# IN_OUT_BIT_7.net
KiCad netlist of a schematic drawn in EasyEDA
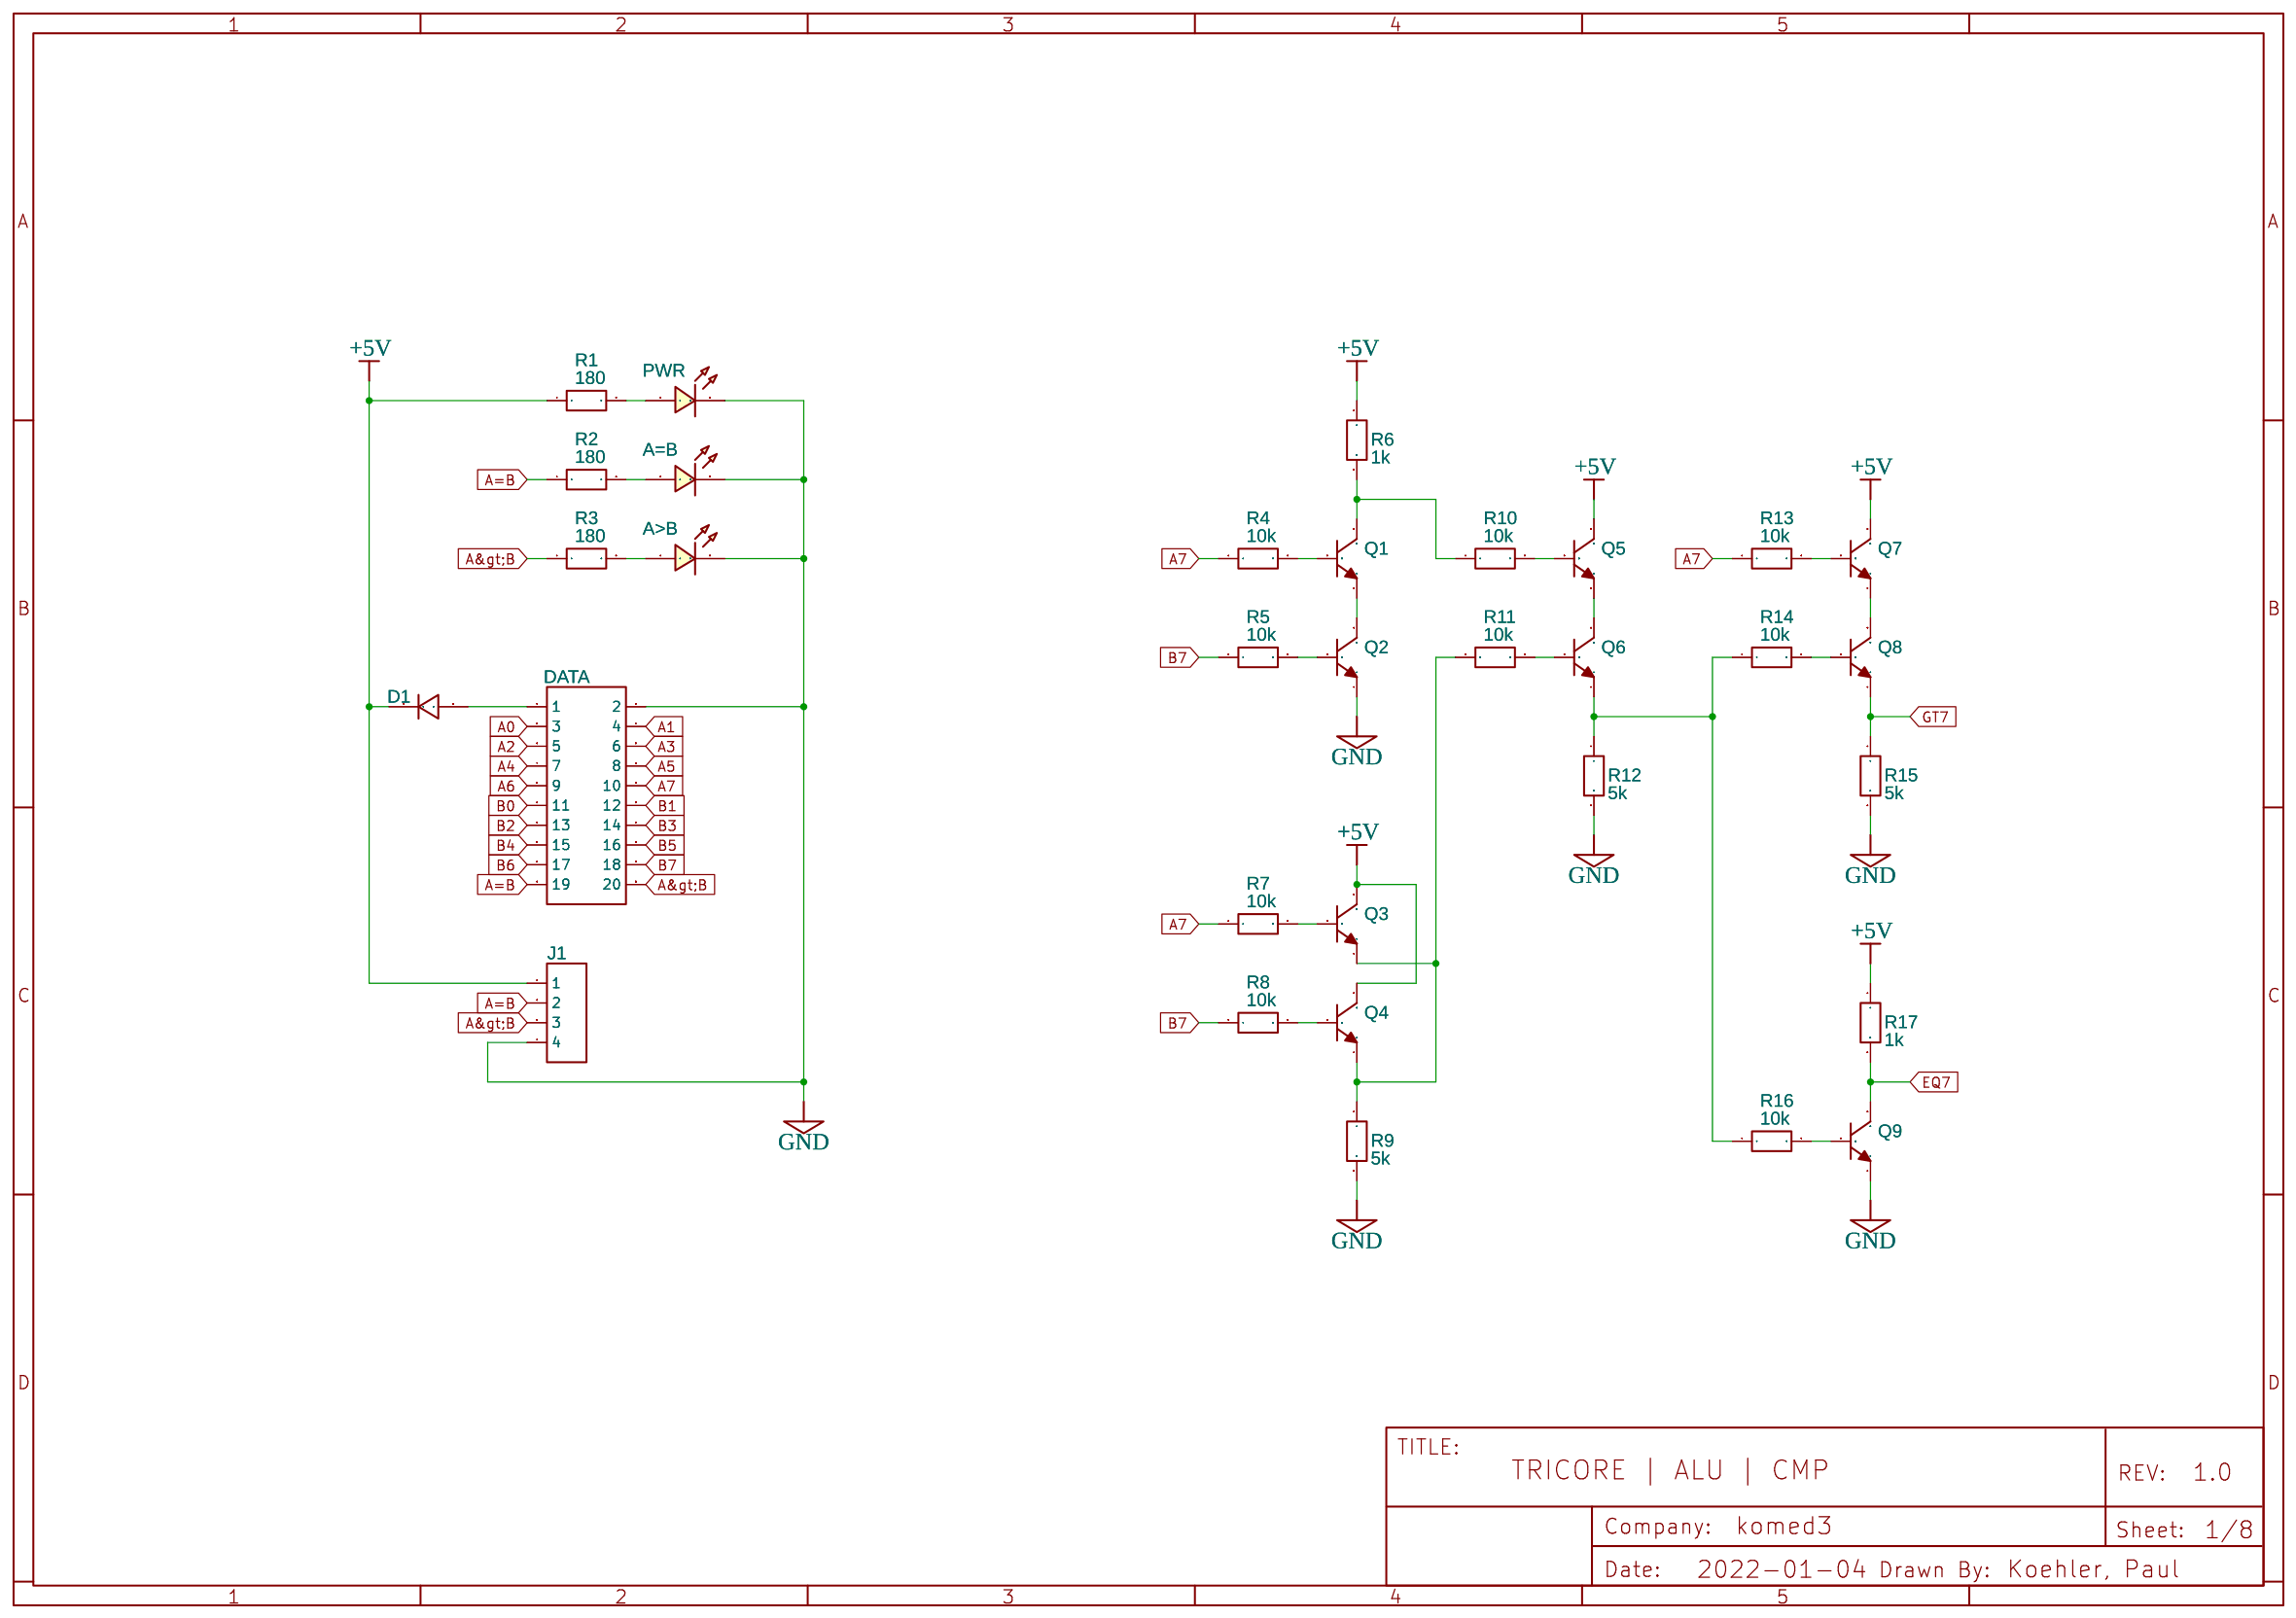
[diagram p0: schematic sheet]

(export (version "E")
  (design (tool "Eeschema 10.0.6"))
  (components
    (comp (ref "A=B")
      (value "LED-TH-5mm_R")
      (fields
        (field (name "BOM_Manufacturer Part") "333-2SURD/S530-A3")
        (field (name "BOM_Supplier Part") "C87271")
      )
      (libsource (lib "") (part "LED-TH-5mm_R"))
    )
    (comp (ref "A>B")
      (value "LED-TH-5mm_R")
      (fields
        (field (name "BOM_Manufacturer Part") "333-2SURD/S530-A3")
        (field (name "BOM_Supplier Part") "C87271")
      )
      (libsource (lib "") (part "LED-TH-5mm_R_1"))
    )
    (comp (ref "D1")
      (value "1N4007")
      (fields (field (name "BOM_Supplier Part") "C106903"))
      (libsource (lib "") (part "1N4007"))
    )
    (comp (ref "DATA")
      (value "HDR-IDC-2.54-2X10P")
      (fields
        (field (name "BOM_Manufacturer Part") "IDC Box 2.54mm 2X10P　Straight")
        (field (name "BOM_Supplier Part") "C3405")
      )
      (libsource (lib "") (part "HDR-IDC-2.54-2X10P"))
    )
    (comp (ref "J1")
      (value "HDR-M-2.54_1x4")
      (fields (field (name "BOM_Supplier Part") "C124378"))
      (libsource (lib "") (part "HDR-M-2.54_1x4"))
    )
    (comp (ref "PWR")
      (value "LED-TH-5mm_R")
      (fields
        (field (name "BOM_Manufacturer Part") "333-2SURD/S530-A3")
        (field (name "BOM_Supplier Part") "C87271")
      )
      (libsource (lib "") (part "LED-TH-5mm_R_2"))
    )
    (comp (ref "Q1")
      (value "2N3904(TO-92)")
      (fields (field (name "BOM_Manufacturer Part") "2N3904") (field (name "BOM_Supplier Part") "C118538"))
      (libsource (lib "") (part "2N3904(TO-92)"))
    )
    (comp (ref "Q2")
      (value "2N3904(TO-92)")
      (fields (field (name "BOM_Manufacturer Part") "2N3904") (field (name "BOM_Supplier Part") "C118538"))
      (libsource (lib "") (part "2N3904(TO-92)"))
    )
    (comp (ref "Q3")
      (value "2N3904(TO-92)")
      (fields (field (name "BOM_Manufacturer Part") "2N3904") (field (name "BOM_Supplier Part") "C118538"))
      (libsource (lib "") (part "2N3904(TO-92)"))
    )
    (comp (ref "Q4")
      (value "2N3904(TO-92)")
      (fields (field (name "BOM_Manufacturer Part") "2N3904") (field (name "BOM_Supplier Part") "C118538"))
      (libsource (lib "") (part "2N3904(TO-92)"))
    )
    (comp (ref "Q5")
      (value "2N3904(TO-92)")
      (fields (field (name "BOM_Manufacturer Part") "2N3904") (field (name "BOM_Supplier Part") "C118538"))
      (libsource (lib "") (part "2N3904(TO-92)"))
    )
    (comp (ref "Q6")
      (value "2N3904(TO-92)")
      (fields (field (name "BOM_Manufacturer Part") "2N3904") (field (name "BOM_Supplier Part") "C118538"))
      (libsource (lib "") (part "2N3904(TO-92)"))
    )
    (comp (ref "Q7")
      (value "2N3904(TO-92)")
      (fields (field (name "BOM_Manufacturer Part") "2N3904") (field (name "BOM_Supplier Part") "C118538"))
      (libsource (lib "") (part "2N3904(TO-92)"))
    )
    (comp (ref "Q8")
      (value "2N3904(TO-92)")
      (fields (field (name "BOM_Manufacturer Part") "2N3904") (field (name "BOM_Supplier Part") "C118538"))
      (libsource (lib "") (part "2N3904(TO-92)"))
    )
    (comp (ref "Q9")
      (value "2N3904(TO-92)")
      (fields (field (name "BOM_Manufacturer Part") "2N3904") (field (name "BOM_Supplier Part") "C118538"))
      (libsource (lib "") (part "2N3904(TO-92)"))
    )
    (comp (ref "R1") (value "180") (libsource (lib "") (part "R_AXIAL-0.3_EU")))
    (comp (ref "R2") (value "180") (libsource (lib "") (part "R_AXIAL-0.3_EU")))
    (comp (ref "R3") (value "180") (libsource (lib "") (part "R_AXIAL-0.3_EU")))
    (comp (ref "R4") (value "10k") (libsource (lib "") (part "R_AXIAL-0.3_EU")))
    (comp (ref "R5") (value "10k") (libsource (lib "") (part "R_AXIAL-0.3_EU")))
    (comp (ref "R6") (value "1k") (libsource (lib "") (part "R_AXIAL-0.3_EU_1")))
    (comp (ref "R7") (value "10k") (libsource (lib "") (part "R_AXIAL-0.3_EU")))
    (comp (ref "R8") (value "10k") (libsource (lib "") (part "R_AXIAL-0.3_EU")))
    (comp (ref "R9") (value "5k") (libsource (lib "") (part "R_AXIAL-0.3_EU_1")))
    (comp (ref "R10") (value "10k") (libsource (lib "") (part "R_AXIAL-0.3_EU")))
    (comp (ref "R11") (value "10k") (libsource (lib "") (part "R_AXIAL-0.3_EU")))
    (comp (ref "R12") (value "5k") (libsource (lib "") (part "R_AXIAL-0.3_EU_1")))
    (comp (ref "R13") (value "10k") (libsource (lib "") (part "R_AXIAL-0.3_EU")))
    (comp (ref "R14") (value "10k") (libsource (lib "") (part "R_AXIAL-0.3_EU")))
    (comp (ref "R15") (value "5k") (libsource (lib "") (part "R_AXIAL-0.3_EU_1")))
    (comp (ref "R16") (value "10k") (libsource (lib "") (part "R_AXIAL-0.3_EU")))
    (comp (ref "R17") (value "1k") (libsource (lib "") (part "R_AXIAL-0.3_EU_1")))
  )
  (nets
    (net (code "1") (name "+5V") (class "Default")
      (node (ref "D1") (pin "1") (pinfunction "1_1") (pintype "unspecified"))
      (node (ref "J1") (pin "1") (pinfunction "1_1") (pintype "unspecified"))
      (node (ref "Q3") (pin "3") (pinfunction "C_3") (pintype "unspecified"))
      (node (ref "Q4") (pin "3") (pinfunction "C_3") (pintype "unspecified"))
      (node (ref "Q5") (pin "3") (pinfunction "C_3") (pintype "unspecified"))
      (node (ref "Q7") (pin "3") (pinfunction "C_3") (pintype "unspecified"))
      (node (ref "R1") (pin "1") (pinfunction "1_1") (pintype "unspecified"))
      (node (ref "R17") (pin "1") (pinfunction "1_1") (pintype "unspecified"))
      (node (ref "R6") (pin "1") (pinfunction "1_1") (pintype "unspecified"))
    )
    (net (code "2") (name "A&gt;B") (class "Default")
      (node (ref "DATA") (pin "20") (pinfunction "20_20") (pintype "unspecified"))
      (node (ref "J1") (pin "3") (pinfunction "3_3") (pintype "unspecified"))
      (node (ref "R3") (pin "1") (pinfunction "1_1") (pintype "unspecified"))
    )
    (net (code "3") (name "A0") (class "Default")
      (node (ref "DATA") (pin "3") (pinfunction "3_3") (pintype "unspecified"))
    )
    (net (code "4") (name "A1") (class "Default")
      (node (ref "DATA") (pin "4") (pinfunction "4_4") (pintype "unspecified"))
    )
    (net (code "5") (name "A2") (class "Default")
      (node (ref "DATA") (pin "5") (pinfunction "5_5") (pintype "unspecified"))
    )
    (net (code "6") (name "A3") (class "Default")
      (node (ref "DATA") (pin "6") (pinfunction "6_6") (pintype "unspecified"))
    )
    (net (code "7") (name "A4") (class "Default")
      (node (ref "DATA") (pin "7") (pinfunction "7_7") (pintype "unspecified"))
    )
    (net (code "8") (name "A5") (class "Default")
      (node (ref "DATA") (pin "8") (pinfunction "8_8") (pintype "unspecified"))
    )
    (net (code "9") (name "A6") (class "Default")
      (node (ref "DATA") (pin "9") (pinfunction "9_9") (pintype "unspecified"))
    )
    (net (code "10") (name "A7") (class "Default")
      (node (ref "DATA") (pin "10") (pinfunction "10_10") (pintype "unspecified"))
      (node (ref "R13") (pin "1") (pinfunction "1_1") (pintype "unspecified"))
      (node (ref "R4") (pin "1") (pinfunction "1_1") (pintype "unspecified"))
      (node (ref "R7") (pin "1") (pinfunction "1_1") (pintype "unspecified"))
    )
    (net (code "11") (name "A=B") (class "Default")
      (node (ref "DATA") (pin "19") (pinfunction "19_19") (pintype "unspecified"))
      (node (ref "J1") (pin "2") (pinfunction "2_2") (pintype "unspecified"))
      (node (ref "R2") (pin "1") (pinfunction "1_1") (pintype "unspecified"))
    )
    (net (code "12") (name "B0") (class "Default")
      (node (ref "DATA") (pin "11") (pinfunction "11_11") (pintype "unspecified"))
    )
    (net (code "13") (name "B1") (class "Default")
      (node (ref "DATA") (pin "12") (pinfunction "12_12") (pintype "unspecified"))
    )
    (net (code "14") (name "B2") (class "Default")
      (node (ref "DATA") (pin "13") (pinfunction "13_13") (pintype "unspecified"))
    )
    (net (code "15") (name "B3") (class "Default")
      (node (ref "DATA") (pin "14") (pinfunction "14_14") (pintype "unspecified"))
    )
    (net (code "16") (name "B4") (class "Default")
      (node (ref "DATA") (pin "15") (pinfunction "15_15") (pintype "unspecified"))
    )
    (net (code "17") (name "B5") (class "Default")
      (node (ref "DATA") (pin "16") (pinfunction "16_16") (pintype "unspecified"))
    )
    (net (code "18") (name "B6") (class "Default")
      (node (ref "DATA") (pin "17") (pinfunction "17_17") (pintype "unspecified"))
    )
    (net (code "19") (name "B7") (class "Default")
      (node (ref "DATA") (pin "18") (pinfunction "18_18") (pintype "unspecified"))
      (node (ref "R5") (pin "1") (pinfunction "1_1") (pintype "unspecified"))
      (node (ref "R8") (pin "1") (pinfunction "1_1") (pintype "unspecified"))
    )
    (net (code "20") (name "EQ7") (class "Default")
      (node (ref "Q9") (pin "3") (pinfunction "C_3") (pintype "unspecified"))
      (node (ref "R17") (pin "2") (pinfunction "2_2") (pintype "unspecified"))
    )
    (net (code "21") (name "GND") (class "Default")
      (node (ref "A=B") (pin "2") (pinfunction "2_2") (pintype "unspecified"))
      (node (ref "A>B") (pin "2") (pinfunction "2_2") (pintype "unspecified"))
      (node (ref "DATA") (pin "2") (pinfunction "2_2") (pintype "unspecified"))
      (node (ref "J1") (pin "4") (pinfunction "4_4") (pintype "unspecified"))
      (node (ref "PWR") (pin "2") (pinfunction "2_2") (pintype "unspecified"))
      (node (ref "Q2") (pin "1") (pinfunction "E_1") (pintype "unspecified"))
      (node (ref "Q9") (pin "1") (pinfunction "E_1") (pintype "unspecified"))
      (node (ref "R12") (pin "2") (pinfunction "2_2") (pintype "unspecified"))
      (node (ref "R15") (pin "2") (pinfunction "2_2") (pintype "unspecified"))
      (node (ref "R9") (pin "2") (pinfunction "2_2") (pintype "unspecified"))
    )
    (net (code "22") (name "GT7") (class "Default")
      (node (ref "Q8") (pin "1") (pinfunction "E_1") (pintype "unspecified"))
      (node (ref "R15") (pin "1") (pinfunction "1_1") (pintype "unspecified"))
    )
    (net (code "23") (name "Net-(A=B-Pad1)") (class "Default")
      (node (ref "A=B") (pin "1") (pinfunction "1_1") (pintype "unspecified"))
      (node (ref "R2") (pin "2") (pinfunction "2_2") (pintype "unspecified"))
    )
    (net (code "24") (name "Net-(A>B-Pad1)") (class "Default")
      (node (ref "A>B") (pin "1") (pinfunction "1_1") (pintype "unspecified"))
      (node (ref "R3") (pin "2") (pinfunction "2_2") (pintype "unspecified"))
    )
    (net (code "25") (name "Net-(D1-Pad2)") (class "Default")
      (node (ref "D1") (pin "2") (pinfunction "2_2") (pintype "unspecified"))
      (node (ref "DATA") (pin "1") (pinfunction "1_1") (pintype "unspecified"))
    )
    (net (code "26") (name "Net-(PWR-Pad1)") (class "Default")
      (node (ref "PWR") (pin "1") (pinfunction "1_1") (pintype "unspecified"))
      (node (ref "R1") (pin "2") (pinfunction "2_2") (pintype "unspecified"))
    )
    (net (code "27") (name "Net-(Q1-B)") (class "Default")
      (node (ref "Q1") (pin "2") (pinfunction "B_2") (pintype "unspecified"))
      (node (ref "R4") (pin "2") (pinfunction "2_2") (pintype "unspecified"))
    )
    (net (code "28") (name "Net-(Q1-C)") (class "Default")
      (node (ref "Q1") (pin "3") (pinfunction "C_3") (pintype "unspecified"))
      (node (ref "R10") (pin "1") (pinfunction "1_1") (pintype "unspecified"))
      (node (ref "R6") (pin "2") (pinfunction "2_2") (pintype "unspecified"))
    )
    (net (code "29") (name "Net-(Q1-E)") (class "Default")
      (node (ref "Q1") (pin "1") (pinfunction "E_1") (pintype "unspecified"))
      (node (ref "Q2") (pin "3") (pinfunction "C_3") (pintype "unspecified"))
    )
    (net (code "30") (name "Net-(Q2-B)") (class "Default")
      (node (ref "Q2") (pin "2") (pinfunction "B_2") (pintype "unspecified"))
      (node (ref "R5") (pin "2") (pinfunction "2_2") (pintype "unspecified"))
    )
    (net (code "31") (name "Net-(Q3-B)") (class "Default")
      (node (ref "Q3") (pin "2") (pinfunction "B_2") (pintype "unspecified"))
      (node (ref "R7") (pin "2") (pinfunction "2_2") (pintype "unspecified"))
    )
    (net (code "32") (name "Net-(Q3-E)") (class "Default")
      (node (ref "Q3") (pin "1") (pinfunction "E_1") (pintype "unspecified"))
      (node (ref "Q4") (pin "1") (pinfunction "E_1") (pintype "unspecified"))
      (node (ref "R11") (pin "1") (pinfunction "1_1") (pintype "unspecified"))
      (node (ref "R9") (pin "1") (pinfunction "1_1") (pintype "unspecified"))
    )
    (net (code "33") (name "Net-(Q4-B)") (class "Default")
      (node (ref "Q4") (pin "2") (pinfunction "B_2") (pintype "unspecified"))
      (node (ref "R8") (pin "2") (pinfunction "2_2") (pintype "unspecified"))
    )
    (net (code "34") (name "Net-(Q5-B)") (class "Default")
      (node (ref "Q5") (pin "2") (pinfunction "B_2") (pintype "unspecified"))
      (node (ref "R10") (pin "2") (pinfunction "2_2") (pintype "unspecified"))
    )
    (net (code "35") (name "Net-(Q5-E)") (class "Default")
      (node (ref "Q5") (pin "1") (pinfunction "E_1") (pintype "unspecified"))
      (node (ref "Q6") (pin "3") (pinfunction "C_3") (pintype "unspecified"))
    )
    (net (code "36") (name "Net-(Q6-B)") (class "Default")
      (node (ref "Q6") (pin "2") (pinfunction "B_2") (pintype "unspecified"))
      (node (ref "R11") (pin "2") (pinfunction "2_2") (pintype "unspecified"))
    )
    (net (code "37") (name "Net-(Q6-E)") (class "Default")
      (node (ref "Q6") (pin "1") (pinfunction "E_1") (pintype "unspecified"))
      (node (ref "R12") (pin "1") (pinfunction "1_1") (pintype "unspecified"))
      (node (ref "R14") (pin "1") (pinfunction "1_1") (pintype "unspecified"))
      (node (ref "R16") (pin "1") (pinfunction "1_1") (pintype "unspecified"))
    )
    (net (code "38") (name "Net-(Q7-B)") (class "Default")
      (node (ref "Q7") (pin "2") (pinfunction "B_2") (pintype "unspecified"))
      (node (ref "R13") (pin "2") (pinfunction "2_2") (pintype "unspecified"))
    )
    (net (code "39") (name "Net-(Q7-E)") (class "Default")
      (node (ref "Q7") (pin "1") (pinfunction "E_1") (pintype "unspecified"))
      (node (ref "Q8") (pin "3") (pinfunction "C_3") (pintype "unspecified"))
    )
    (net (code "40") (name "Net-(Q8-B)") (class "Default")
      (node (ref "Q8") (pin "2") (pinfunction "B_2") (pintype "unspecified"))
      (node (ref "R14") (pin "2") (pinfunction "2_2") (pintype "unspecified"))
    )
    (net (code "41") (name "Net-(Q9-B)") (class "Default")
      (node (ref "Q9") (pin "2") (pinfunction "B_2") (pintype "unspecified"))
      (node (ref "R16") (pin "2") (pinfunction "2_2") (pintype "unspecified"))
    )
  )
)
